# MCB-NINA-B1-v2_0_0.net
KiCad netlist of a schematic drawn in EAGLE
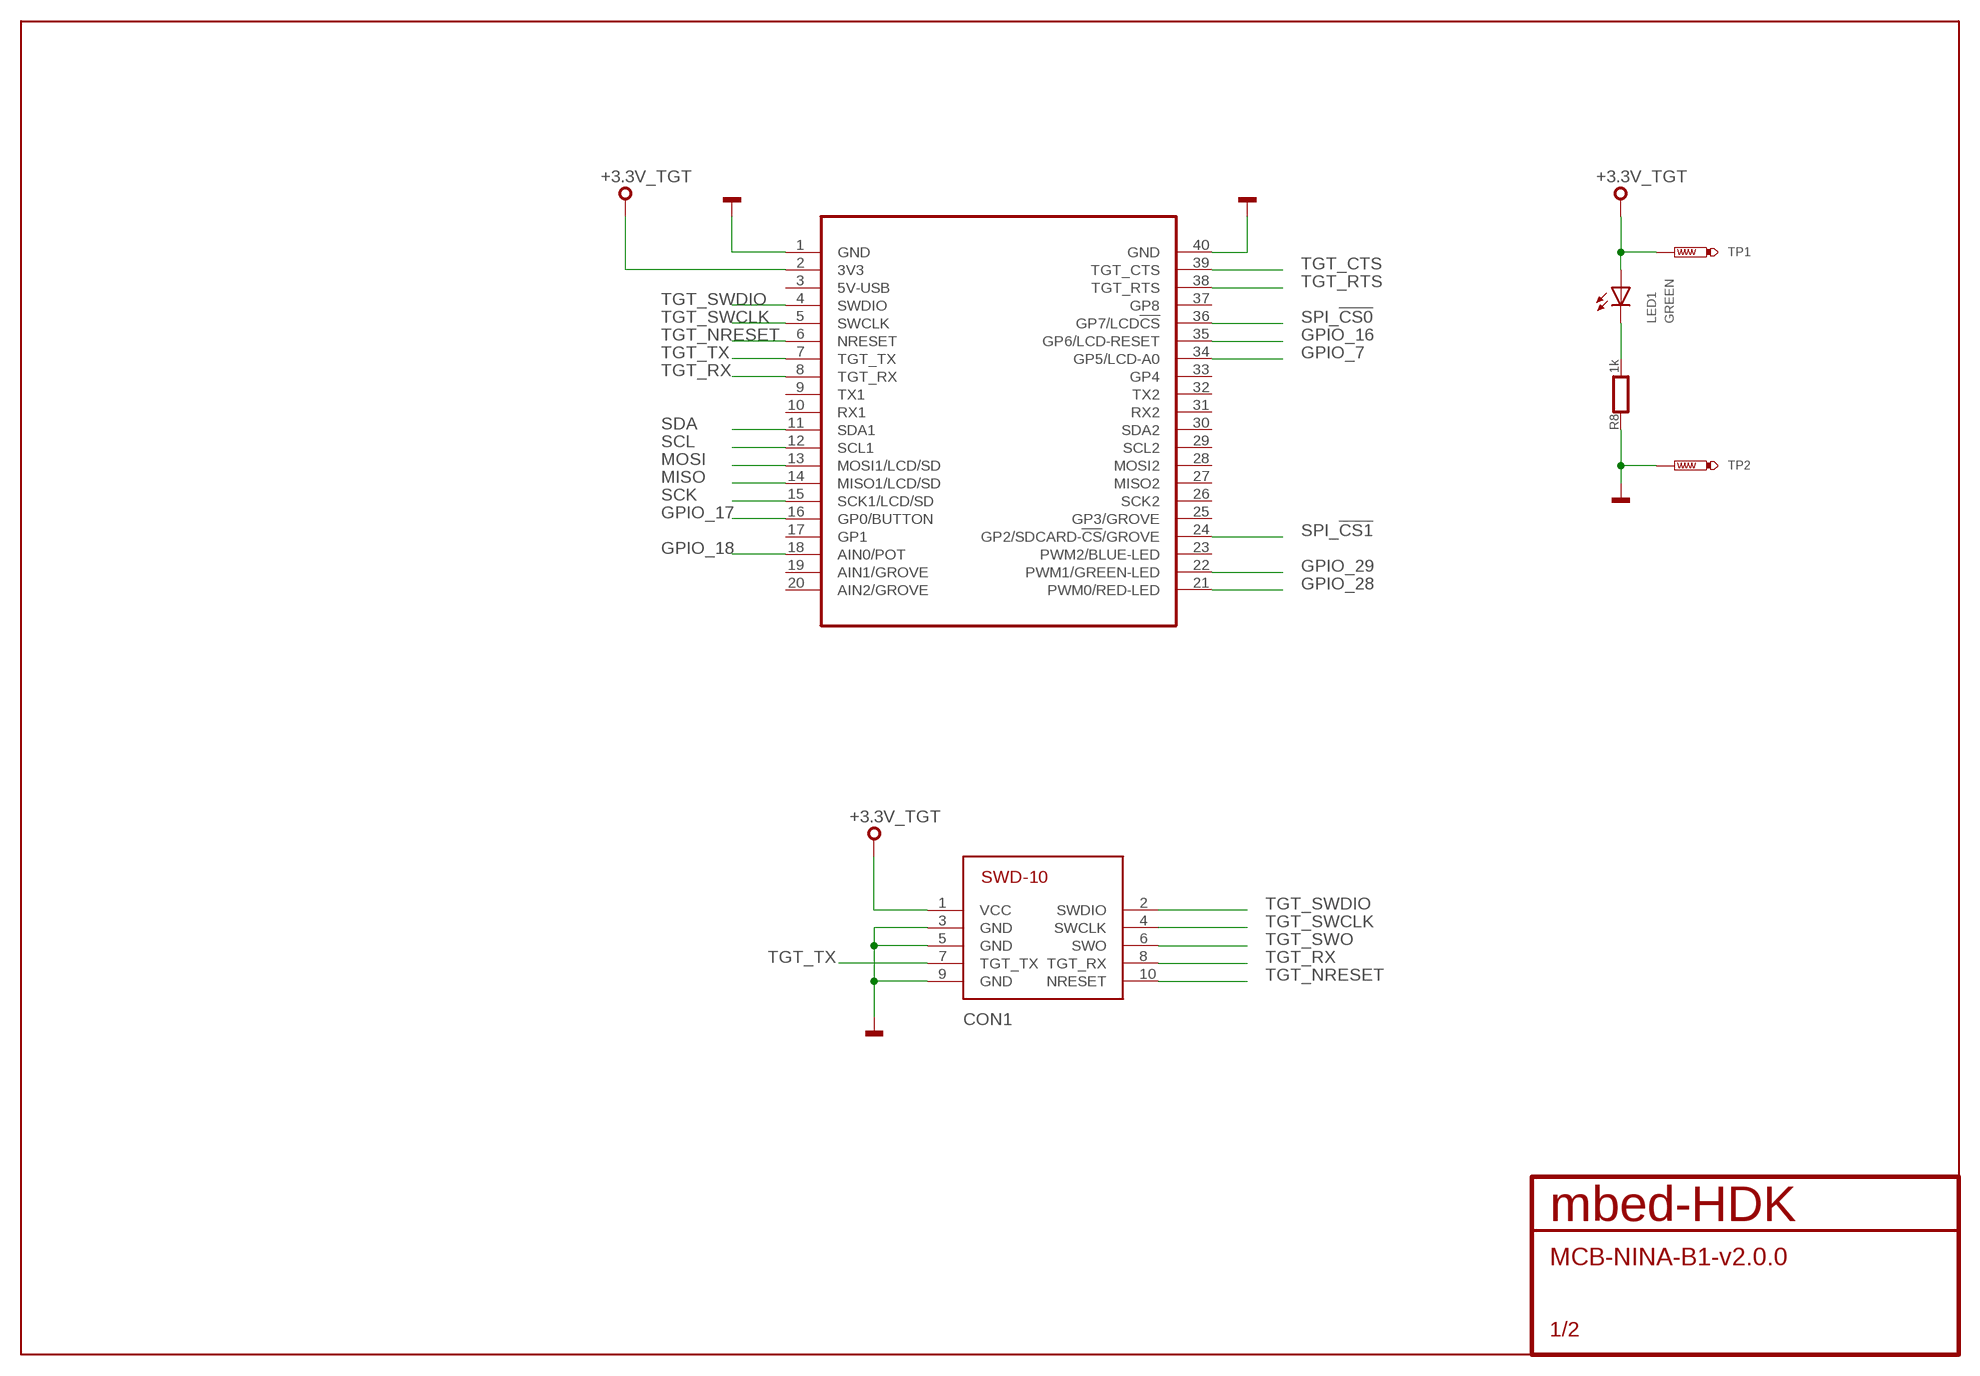
[diagram p0: schematic, sheet 1]
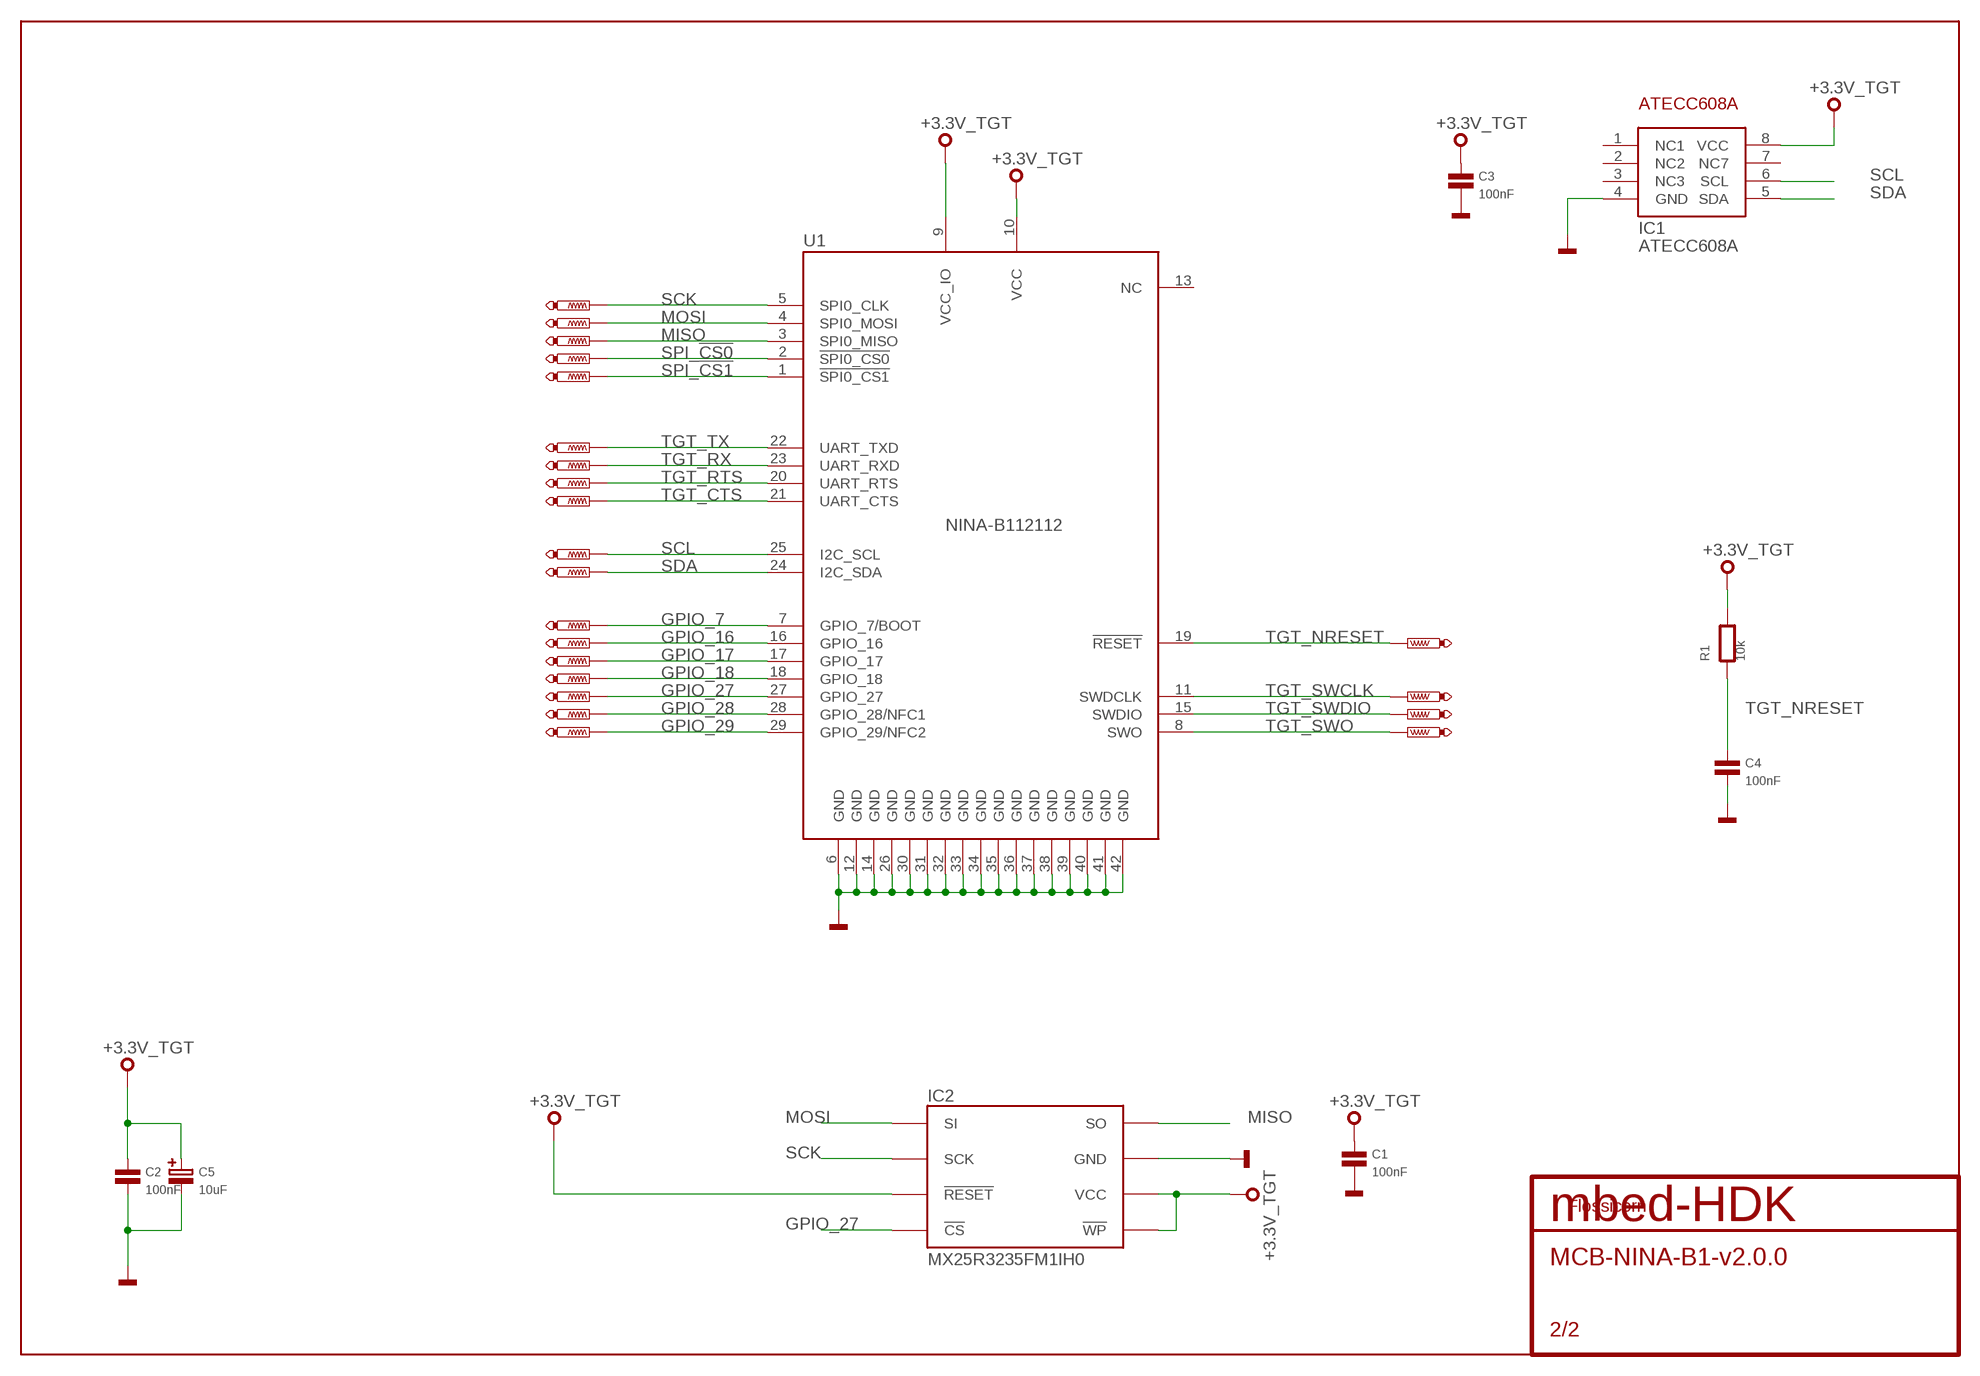
[diagram p1: schematic, sheet 2]

(export (version "E")
  (design (tool "Eeschema 10.0.6"))
  (components
    (comp (ref "CON1")
      (value "SWD-10/TC2050_SMD")
      (footprint "eagle-import:FTSH-105-02")
      (libsource (lib "eagle-import") (part "SWD-10/TC2050_SMD"))
    )
    (comp (ref "LED1")
      (value "GREEN")
      (footprint "eagle-import:CHIPLED_0603")
      (fields (field (name "MF") "Wurth Electronics Inc"))
      (libsource (lib "eagle-import") (part "SMD_LED0603"))
    )
    (comp (ref "MOD1")
      (value "MODULE_DAUGHTER")
      (footprint "eagle-import:MODULE_DAUGHTER")
      (libsource (lib "eagle-import") (part "MODULE_DAUGHTER"))
    )
    (comp (ref "R8")
      (value "1k")
      (footprint "eagle-import:0603")
      (libsource (lib "eagle-import") (part "RESISTOR0603"))
    )
    (comp (ref "TP1")
      (value "TEST-POINT-50R-PTH")
      (footprint "eagle-import:TP50-PTH")
      (libsource (lib "eagle-import") (part "TEST-POINT-50R-PTH"))
    )
    (comp (ref "TP2")
      (value "TEST-POINT-50R-PTH")
      (footprint "eagle-import:TP50-PTH")
      (libsource (lib "eagle-import") (part "TEST-POINT-50R-PTH"))
    )
    (comp (ref "C1")
      (value "100nF")
      (footprint "eagle-import:0603")
      (libsource (lib "eagle-import") (part "CAPACITOR0603"))
    )
    (comp (ref "C2")
      (value "100nF")
      (footprint "eagle-import:0603")
      (libsource (lib "eagle-import") (part "CAPACITOR0603"))
    )
    (comp (ref "C3")
      (value "100nF")
      (footprint "eagle-import:0603")
      (libsource (lib "eagle-import") (part "CAPACITOR0603"))
    )
    (comp (ref "C4")
      (value "100nF")
      (footprint "eagle-import:0603")
      (libsource (lib "eagle-import") (part "CAPACITOR0603"))
    )
    (comp (ref "C5")
      (value "10uF")
      (footprint "eagle-import:SMC_B")
      (fields (field (name "MF") "Kemet"))
      (libsource (lib "eagle-import") (part "CAPACITOR-POLARISEDB"))
    )
    (comp (ref "IC1")
      (value "ATECC608A")
      (footprint "eagle-import:SO8")
      (libsource (lib "eagle-import") (part "ATECC608A"))
    )
    (comp (ref "IC2")
      (value "MX25R3235FM1IH0")
      (footprint "eagle-import:SO8")
      (fields (field (name "MF") "Macronix"))
      (libsource (lib "eagle-import") (part "MX25R3235FM1IH0"))
    )
    (comp (ref "R1")
      (value "10k")
      (footprint "eagle-import:0603")
      (libsource (lib "eagle-import") (part "RESISTOR0603"))
    )
    (comp (ref "SS1")
      (value "FLOSSICORN0.5")
      (footprint "eagle-import:FLOSSICORN-0.5")
      (libsource (lib "eagle-import") (part "FLOSSICORN0.5"))
    )
    (comp (ref "TP3")
      (value "PTR1B1,27")
      (footprint "eagle-import:B1,27")
      (libsource (lib "eagle-import") (part "PTR1B1,27"))
    )
    (comp (ref "TP4")
      (value "PTR1B1,27")
      (footprint "eagle-import:B1,27")
      (libsource (lib "eagle-import") (part "PTR1B1,27"))
    )
    (comp (ref "TP5")
      (value "PTR1B1,27")
      (footprint "eagle-import:B1,27")
      (libsource (lib "eagle-import") (part "PTR1B1,27"))
    )
    (comp (ref "TP6")
      (value "PTR1B1,27")
      (footprint "eagle-import:B1,27")
      (libsource (lib "eagle-import") (part "PTR1B1,27"))
    )
    (comp (ref "TP7")
      (value "PTR1B1,27")
      (footprint "eagle-import:B1,27")
      (libsource (lib "eagle-import") (part "PTR1B1,27"))
    )
    (comp (ref "TP8")
      (value "PTR1B1,27")
      (footprint "eagle-import:B1,27")
      (libsource (lib "eagle-import") (part "PTR1B1,27"))
    )
    (comp (ref "TP9")
      (value "PTR1B1,27")
      (footprint "eagle-import:B1,27")
      (libsource (lib "eagle-import") (part "PTR1B1,27"))
    )
    (comp (ref "TP10")
      (value "PTR1B1,27")
      (footprint "eagle-import:B1,27")
      (libsource (lib "eagle-import") (part "PTR1B1,27"))
    )
    (comp (ref "TP11")
      (value "PTR1B1,27")
      (footprint "eagle-import:B1,27")
      (libsource (lib "eagle-import") (part "PTR1B1,27"))
    )
    (comp (ref "TP12")
      (value "PTR1B1,27")
      (footprint "eagle-import:B1,27")
      (libsource (lib "eagle-import") (part "PTR1B1,27"))
    )
    (comp (ref "TP13")
      (value "PTR1B1,27")
      (footprint "eagle-import:B1,27")
      (libsource (lib "eagle-import") (part "PTR1B1,27"))
    )
    (comp (ref "TP14")
      (value "PTR1B1,27")
      (footprint "eagle-import:B1,27")
      (libsource (lib "eagle-import") (part "PTR1B1,27"))
    )
    (comp (ref "TP15")
      (value "PTR1B1,27")
      (footprint "eagle-import:B1,27")
      (libsource (lib "eagle-import") (part "PTR1B1,27"))
    )
    (comp (ref "TP16")
      (value "PTR1B1,27")
      (footprint "eagle-import:B1,27")
      (libsource (lib "eagle-import") (part "PTR1B1,27"))
    )
    (comp (ref "TP17")
      (value "PTR1B1,27")
      (footprint "eagle-import:B1,27")
      (libsource (lib "eagle-import") (part "PTR1B1,27"))
    )
    (comp (ref "TP18")
      (value "PTR1B1,27")
      (footprint "eagle-import:B1,27")
      (libsource (lib "eagle-import") (part "PTR1B1,27"))
    )
    (comp (ref "TP19")
      (value "PTR1B1,27")
      (footprint "eagle-import:B1,27")
      (libsource (lib "eagle-import") (part "PTR1B1,27"))
    )
    (comp (ref "TP20")
      (value "PTR1B1,27")
      (footprint "eagle-import:B1,27")
      (libsource (lib "eagle-import") (part "PTR1B1,27"))
    )
    (comp (ref "TP21")
      (value "PTR1B1,27")
      (footprint "eagle-import:B1,27")
      (libsource (lib "eagle-import") (part "PTR1B1,27"))
    )
    (comp (ref "TP22")
      (value "PTR1B1,27")
      (footprint "eagle-import:B1,27")
      (libsource (lib "eagle-import") (part "PTR1B1,27"))
    )
    (comp (ref "TP23")
      (value "PTR1B1,27")
      (footprint "eagle-import:B1,27")
      (libsource (lib "eagle-import") (part "PTR1B1,27"))
    )
    (comp (ref "TP24")
      (value "PTR1B1,27")
      (footprint "eagle-import:B1,27")
      (libsource (lib "eagle-import") (part "PTR1B1,27"))
    )
    (comp (ref "U1")
      (value "NINA-B112112")
      (footprint "eagle-import:NINA112-42")
      (libsource (lib "eagle-import") (part "NINA-B112112"))
    )
  )
  (nets
    (net (code "1") (name "+3.3V_TGT") (class "Default")
      (node (ref "C1") (pin "1") (pinfunction "P$1_1") (pintype "passive"))
      (node (ref "C2") (pin "1") (pinfunction "P$1_1") (pintype "passive"))
      (node (ref "C3") (pin "1") (pinfunction "P$1_1") (pintype "passive"))
      (node (ref "C5") (pin "+") (pinfunction "+_+") (pintype "passive"))
      (node (ref "CON1") (pin "1") (pinfunction "VCC_1") (pintype "bidirectional"))
      (node (ref "IC1") (pin "8") (pinfunction "VCC_8") (pintype "bidirectional"))
      (node (ref "IC2") (pin "3") (pinfunction "~{WP}_3") (pintype "bidirectional"))
      (node (ref "IC2") (pin "7") (pinfunction "~{RESET}_7") (pintype "bidirectional"))
      (node (ref "IC2") (pin "8") (pinfunction "VCC_8") (pintype "bidirectional"))
      (node (ref "LED1") (pin "A") (pinfunction "A_A") (pintype "passive"))
      (node (ref "MOD1") (pin "2") (pinfunction "3V3_2") (pintype "bidirectional"))
      (node (ref "R1") (pin "2") (pinfunction "P$2_2") (pintype "passive"))
      (node (ref "TP1") (pin "TP") (pinfunction "TP_TP") (pintype "input"))
      (node (ref "U1") (pin "10") (pinfunction "VCC_10") (pintype "power_in"))
      (node (ref "U1") (pin "9") (pinfunction "VCC_IO_9") (pintype "power_in"))
    )
    (net (code "2") (name "GND") (class "Default")
      (node (ref "C1") (pin "2") (pinfunction "P$2_2") (pintype "passive"))
      (node (ref "C2") (pin "2") (pinfunction "P$2_2") (pintype "passive"))
      (node (ref "C3") (pin "2") (pinfunction "P$2_2") (pintype "passive"))
      (node (ref "C4") (pin "2") (pinfunction "P$2_2") (pintype "passive"))
      (node (ref "C5") (pin "-") (pinfunction "-_-") (pintype "passive"))
      (node (ref "CON1") (pin "3") (pinfunction "GND_3") (pintype "bidirectional"))
      (node (ref "CON1") (pin "5") (pinfunction "GND_5") (pintype "bidirectional"))
      (node (ref "CON1") (pin "9") (pinfunction "GND_9") (pintype "bidirectional"))
      (node (ref "IC1") (pin "4") (pinfunction "GND_4") (pintype "bidirectional"))
      (node (ref "IC2") (pin "4") (pinfunction "GND_4") (pintype "bidirectional"))
      (node (ref "MOD1") (pin "1") (pinfunction "GND_1") (pintype "bidirectional"))
      (node (ref "MOD1") (pin "40") (pinfunction "GND_40") (pintype "bidirectional"))
      (node (ref "R8") (pin "1") (pinfunction "P$1_1") (pintype "passive"))
      (node (ref "TP2") (pin "TP") (pinfunction "TP_TP") (pintype "input"))
      (node (ref "U1") (pin "12") (pinfunction "GND_12") (pintype "power_in"))
      (node (ref "U1") (pin "14") (pinfunction "GND_14") (pintype "power_in"))
      (node (ref "U1") (pin "26") (pinfunction "GND_26") (pintype "power_in"))
      (node (ref "U1") (pin "30") (pinfunction "GND_30") (pintype "power_in"))
      (node (ref "U1") (pin "31") (pinfunction "GND_31") (pintype "power_in"))
      (node (ref "U1") (pin "32") (pinfunction "GND_32") (pintype "power_in"))
      (node (ref "U1") (pin "33") (pinfunction "GND_33") (pintype "power_in"))
      (node (ref "U1") (pin "34") (pinfunction "GND_34") (pintype "power_in"))
      (node (ref "U1") (pin "35") (pinfunction "GND_35") (pintype "power_in"))
      (node (ref "U1") (pin "36") (pinfunction "GND_36") (pintype "power_in"))
      (node (ref "U1") (pin "37") (pinfunction "GND_37") (pintype "power_in"))
      (node (ref "U1") (pin "38") (pinfunction "GND_38") (pintype "power_in"))
      (node (ref "U1") (pin "39") (pinfunction "GND_39") (pintype "power_in"))
      (node (ref "U1") (pin "40") (pinfunction "GND_40") (pintype "power_in"))
      (node (ref "U1") (pin "41") (pinfunction "GND_41") (pintype "power_in"))
      (node (ref "U1") (pin "42") (pinfunction "GND_42") (pintype "power_in"))
      (node (ref "U1") (pin "6") (pinfunction "GND_6") (pintype "power_in"))
    )
    (net (code "3") (name "GPIO_7") (class "Default")
      (node (ref "MOD1") (pin "34") (pinfunction "GP5/LCD-A0_34") (pintype "bidirectional"))
      (node (ref "TP14") (pin "TP") (pinfunction "TP_TP") (pintype "input"))
      (node (ref "U1") (pin "7") (pinfunction "GPIO_7/BOOT_7") (pintype "bidirectional"))
    )
    (net (code "4") (name "GPIO_16") (class "Default")
      (node (ref "MOD1") (pin "35") (pinfunction "GP6/LCD-RESET_35") (pintype "bidirectional"))
      (node (ref "TP15") (pin "TP") (pinfunction "TP_TP") (pintype "input"))
      (node (ref "U1") (pin "16") (pinfunction "GPIO_16_16") (pintype "bidirectional"))
    )
    (net (code "5") (name "GPIO_17") (class "Default")
      (node (ref "MOD1") (pin "16") (pinfunction "GP0/BUTTON_16") (pintype "bidirectional"))
      (node (ref "TP16") (pin "TP") (pinfunction "TP_TP") (pintype "input"))
      (node (ref "U1") (pin "17") (pinfunction "GPIO_17_17") (pintype "bidirectional"))
    )
    (net (code "6") (name "GPIO_18") (class "Default")
      (node (ref "MOD1") (pin "18") (pinfunction "AIN0/POT_18") (pintype "bidirectional"))
      (node (ref "TP17") (pin "TP") (pinfunction "TP_TP") (pintype "input"))
      (node (ref "U1") (pin "18") (pinfunction "GPIO_18_18") (pintype "bidirectional"))
    )
    (net (code "7") (name "GPIO_27") (class "Default")
      (node (ref "IC2") (pin "1") (pinfunction "~{CS}_1") (pintype "bidirectional"))
      (node (ref "TP18") (pin "TP") (pinfunction "TP_TP") (pintype "input"))
      (node (ref "U1") (pin "27") (pinfunction "GPIO_27_27") (pintype "bidirectional"))
    )
    (net (code "8") (name "GPIO_28") (class "Default")
      (node (ref "MOD1") (pin "21") (pinfunction "PWM0/RED-LED_21") (pintype "bidirectional"))
      (node (ref "TP19") (pin "TP") (pinfunction "TP_TP") (pintype "input"))
      (node (ref "U1") (pin "28") (pinfunction "GPIO_28/NFC1_28") (pintype "bidirectional"))
    )
    (net (code "9") (name "GPIO_29") (class "Default")
      (node (ref "MOD1") (pin "22") (pinfunction "PWM1/GREEN-LED_22") (pintype "bidirectional"))
      (node (ref "TP20") (pin "TP") (pinfunction "TP_TP") (pintype "input"))
      (node (ref "U1") (pin "29") (pinfunction "GPIO_29/NFC2_29") (pintype "bidirectional"))
    )
    (net (code "10") (name "MISO") (class "Default")
      (node (ref "IC2") (pin "2") (pinfunction "SO_2") (pintype "bidirectional"))
      (node (ref "MOD1") (pin "14") (pinfunction "MISO1/LCD/SD_14") (pintype "bidirectional"))
      (node (ref "TP5") (pin "TP") (pinfunction "TP_TP") (pintype "input"))
      (node (ref "U1") (pin "3") (pinfunction "SPI0_MISO_3") (pintype "bidirectional"))
    )
    (net (code "11") (name "MOSI") (class "Default")
      (node (ref "IC2") (pin "5") (pinfunction "SI_5") (pintype "bidirectional"))
      (node (ref "MOD1") (pin "13") (pinfunction "MOSI1/LCD/SD_13") (pintype "bidirectional"))
      (node (ref "TP4") (pin "TP") (pinfunction "TP_TP") (pintype "input"))
      (node (ref "U1") (pin "4") (pinfunction "SPI0_MOSI_4") (pintype "bidirectional"))
    )
    (net (code "12") (name "Net-(R8-P$2)") (class "Default")
      (node (ref "LED1") (pin "C") (pinfunction "C_C") (pintype "passive"))
      (node (ref "R8") (pin "2") (pinfunction "P$2_2") (pintype "passive"))
    )
    (net (code "13") (name "SCK") (class "Default")
      (node (ref "IC2") (pin "6") (pinfunction "SCK_6") (pintype "bidirectional"))
      (node (ref "MOD1") (pin "15") (pinfunction "SCK1/LCD/SD_15") (pintype "bidirectional"))
      (node (ref "TP3") (pin "TP") (pinfunction "TP_TP") (pintype "input"))
      (node (ref "U1") (pin "5") (pinfunction "SPI0_CLK_5") (pintype "bidirectional"))
    )
    (net (code "14") (name "SCL") (class "Default")
      (node (ref "IC1") (pin "6") (pinfunction "SCL_6") (pintype "bidirectional"))
      (node (ref "MOD1") (pin "12") (pinfunction "SCL1_12") (pintype "bidirectional"))
      (node (ref "TP12") (pin "TP") (pinfunction "TP_TP") (pintype "input"))
      (node (ref "U1") (pin "25") (pinfunction "I2C_SCL_25") (pintype "bidirectional"))
    )
    (net (code "15") (name "SDA") (class "Default")
      (node (ref "IC1") (pin "5") (pinfunction "SDA_5") (pintype "bidirectional"))
      (node (ref "MOD1") (pin "11") (pinfunction "SDA1_11") (pintype "bidirectional"))
      (node (ref "TP13") (pin "TP") (pinfunction "TP_TP") (pintype "input"))
      (node (ref "U1") (pin "24") (pinfunction "I2C_SDA_24") (pintype "bidirectional"))
    )
    (net (code "16") (name "SPI_~{CS0}") (class "Default")
      (node (ref "MOD1") (pin "36") (pinfunction "GP7/LCD~{CS}_36") (pintype "bidirectional"))
      (node (ref "TP6") (pin "TP") (pinfunction "TP_TP") (pintype "input"))
      (node (ref "U1") (pin "2") (pinfunction "~{SPI0_CS0}_2") (pintype "bidirectional"))
    )
    (net (code "17") (name "SPI_~{CS1}") (class "Default")
      (node (ref "MOD1") (pin "24") (pinfunction "GP2/SDCARD-~{CS}/GROVE_24") (pintype "bidirectional"))
      (node (ref "TP7") (pin "TP") (pinfunction "TP_TP") (pintype "input"))
      (node (ref "U1") (pin "1") (pinfunction "~{SPI0_CS1}_1") (pintype "output"))
    )
    (net (code "18") (name "TGT_CTS") (class "Default")
      (node (ref "MOD1") (pin "39") (pinfunction "TGT_CTS_39") (pintype "bidirectional"))
      (node (ref "TP11") (pin "TP") (pinfunction "TP_TP") (pintype "input"))
      (node (ref "U1") (pin "21") (pinfunction "UART_CTS_21") (pintype "bidirectional"))
    )
    (net (code "19") (name "TGT_NRESET") (class "Default")
      (node (ref "C4") (pin "1") (pinfunction "P$1_1") (pintype "passive"))
      (node (ref "CON1") (pin "10") (pinfunction "NRESET_10") (pintype "bidirectional"))
      (node (ref "MOD1") (pin "6") (pinfunction "NRESET_6") (pintype "bidirectional"))
      (node (ref "R1") (pin "1") (pinfunction "P$1_1") (pintype "passive"))
      (node (ref "TP21") (pin "TP") (pinfunction "TP_TP") (pintype "input"))
      (node (ref "U1") (pin "19") (pinfunction "~{RESET}_19") (pintype "input"))
    )
    (net (code "20") (name "TGT_RTS") (class "Default")
      (node (ref "MOD1") (pin "38") (pinfunction "TGT_RTS_38") (pintype "bidirectional"))
      (node (ref "TP10") (pin "TP") (pinfunction "TP_TP") (pintype "input"))
      (node (ref "U1") (pin "20") (pinfunction "UART_RTS_20") (pintype "bidirectional"))
    )
    (net (code "21") (name "TGT_RX") (class "Default")
      (node (ref "CON1") (pin "8") (pinfunction "TGT_RX_8") (pintype "bidirectional"))
      (node (ref "MOD1") (pin "8") (pinfunction "TGT_RX_8") (pintype "bidirectional"))
      (node (ref "TP9") (pin "TP") (pinfunction "TP_TP") (pintype "input"))
      (node (ref "U1") (pin "23") (pinfunction "UART_RXD_23") (pintype "bidirectional"))
    )
    (net (code "22") (name "TGT_SWCLK") (class "Default")
      (node (ref "CON1") (pin "4") (pinfunction "SWCLK_4") (pintype "bidirectional"))
      (node (ref "MOD1") (pin "5") (pinfunction "SWCLK_5") (pintype "bidirectional"))
      (node (ref "TP22") (pin "TP") (pinfunction "TP_TP") (pintype "input"))
      (node (ref "U1") (pin "11") (pinfunction "SWDCLK_11") (pintype "input"))
    )
    (net (code "23") (name "TGT_SWDIO") (class "Default")
      (node (ref "CON1") (pin "2") (pinfunction "SWDIO_2") (pintype "bidirectional"))
      (node (ref "MOD1") (pin "4") (pinfunction "SWDIO_4") (pintype "bidirectional"))
      (node (ref "TP23") (pin "TP") (pinfunction "TP_TP") (pintype "input"))
      (node (ref "U1") (pin "15") (pinfunction "SWDIO_15") (pintype "bidirectional"))
    )
    (net (code "24") (name "TGT_SWO") (class "Default")
      (node (ref "CON1") (pin "6") (pinfunction "SWO_6") (pintype "bidirectional"))
      (node (ref "TP24") (pin "TP") (pinfunction "TP_TP") (pintype "input"))
      (node (ref "U1") (pin "8") (pinfunction "SWO_8") (pintype "output"))
    )
    (net (code "25") (name "TGT_TX") (class "Default")
      (node (ref "CON1") (pin "7") (pinfunction "TGT_TX_7") (pintype "bidirectional"))
      (node (ref "MOD1") (pin "7") (pinfunction "TGT_TX_7") (pintype "bidirectional"))
      (node (ref "TP8") (pin "TP") (pinfunction "TP_TP") (pintype "input"))
      (node (ref "U1") (pin "22") (pinfunction "UART_TXD_22") (pintype "bidirectional"))
    )
    (net (code "26") (name "unconnected-(IC1-NC1-Pad1)") (class "Default")
      (node (ref "IC1") (pin "1") (pinfunction "NC1_1") (pintype "bidirectional"))
    )
    (net (code "27") (name "unconnected-(IC1-NC2-Pad2)") (class "Default")
      (node (ref "IC1") (pin "2") (pinfunction "NC2_2") (pintype "bidirectional"))
    )
    (net (code "28") (name "unconnected-(IC1-NC3-Pad3)") (class "Default")
      (node (ref "IC1") (pin "3") (pinfunction "NC3_3") (pintype "bidirectional"))
    )
    (net (code "29") (name "unconnected-(IC1-NC7-Pad7)") (class "Default")
      (node (ref "IC1") (pin "7") (pinfunction "NC7_7") (pintype "bidirectional"))
    )
    (net (code "30") (name "unconnected-(MOD1-5V-USB-Pad3)") (class "Default")
      (node (ref "MOD1") (pin "3") (pinfunction "5V-USB_3") (pintype "bidirectional"))
    )
    (net (code "31") (name "unconnected-(MOD1-AIN1{slash}GROVE-Pad19)") (class "Default")
      (node (ref "MOD1") (pin "19") (pinfunction "AIN1/GROVE_19") (pintype "bidirectional"))
    )
    (net (code "32") (name "unconnected-(MOD1-AIN2{slash}GROVE-Pad20)") (class "Default")
      (node (ref "MOD1") (pin "20") (pinfunction "AIN2/GROVE_20") (pintype "bidirectional"))
    )
    (net (code "33") (name "unconnected-(MOD1-GP1-Pad17)") (class "Default")
      (node (ref "MOD1") (pin "17") (pinfunction "GP1_17") (pintype "bidirectional"))
    )
    (net (code "34") (name "unconnected-(MOD1-GP3{slash}GROVE-Pad25)") (class "Default")
      (node (ref "MOD1") (pin "25") (pinfunction "GP3/GROVE_25") (pintype "bidirectional"))
    )
    (net (code "35") (name "unconnected-(MOD1-GP4-Pad33)") (class "Default")
      (node (ref "MOD1") (pin "33") (pinfunction "GP4_33") (pintype "bidirectional"))
    )
    (net (code "36") (name "unconnected-(MOD1-GP8-Pad37)") (class "Default")
      (node (ref "MOD1") (pin "37") (pinfunction "GP8_37") (pintype "bidirectional"))
    )
    (net (code "37") (name "unconnected-(MOD1-MISO2-Pad27)") (class "Default")
      (node (ref "MOD1") (pin "27") (pinfunction "MISO2_27") (pintype "bidirectional"))
    )
    (net (code "38") (name "unconnected-(MOD1-MOSI2-Pad28)") (class "Default")
      (node (ref "MOD1") (pin "28") (pinfunction "MOSI2_28") (pintype "bidirectional"))
    )
    (net (code "39") (name "unconnected-(MOD1-PWM2{slash}BLUE-LED-Pad23)") (class "Default")
      (node (ref "MOD1") (pin "23") (pinfunction "PWM2/BLUE-LED_23") (pintype "bidirectional"))
    )
    (net (code "40") (name "unconnected-(MOD1-RX1-Pad10)") (class "Default")
      (node (ref "MOD1") (pin "10") (pinfunction "RX1_10") (pintype "bidirectional"))
    )
    (net (code "41") (name "unconnected-(MOD1-RX2-Pad31)") (class "Default")
      (node (ref "MOD1") (pin "31") (pinfunction "RX2_31") (pintype "bidirectional"))
    )
    (net (code "42") (name "unconnected-(MOD1-SCK2-Pad26)") (class "Default")
      (node (ref "MOD1") (pin "26") (pinfunction "SCK2_26") (pintype "bidirectional"))
    )
    (net (code "43") (name "unconnected-(MOD1-SCL2-Pad29)") (class "Default")
      (node (ref "MOD1") (pin "29") (pinfunction "SCL2_29") (pintype "bidirectional"))
    )
    (net (code "44") (name "unconnected-(MOD1-SDA2-Pad30)") (class "Default")
      (node (ref "MOD1") (pin "30") (pinfunction "SDA2_30") (pintype "bidirectional"))
    )
    (net (code "45") (name "unconnected-(MOD1-TX1-Pad9)") (class "Default")
      (node (ref "MOD1") (pin "9") (pinfunction "TX1_9") (pintype "bidirectional"))
    )
    (net (code "46") (name "unconnected-(MOD1-TX2-Pad32)") (class "Default")
      (node (ref "MOD1") (pin "32") (pinfunction "TX2_32") (pintype "bidirectional"))
    )
    (net (code "47") (name "unconnected-(U1-NC-Pad13)") (class "Default")
      (node (ref "U1") (pin "13") (pinfunction "NC_13") (pintype "no_connect"))
    )
  )
)
